# ALLPRINT-CAPBOARD-677512-SIGNAL-INPUTS.net
KiCad netlist of a schematic drawn in Altium Designer
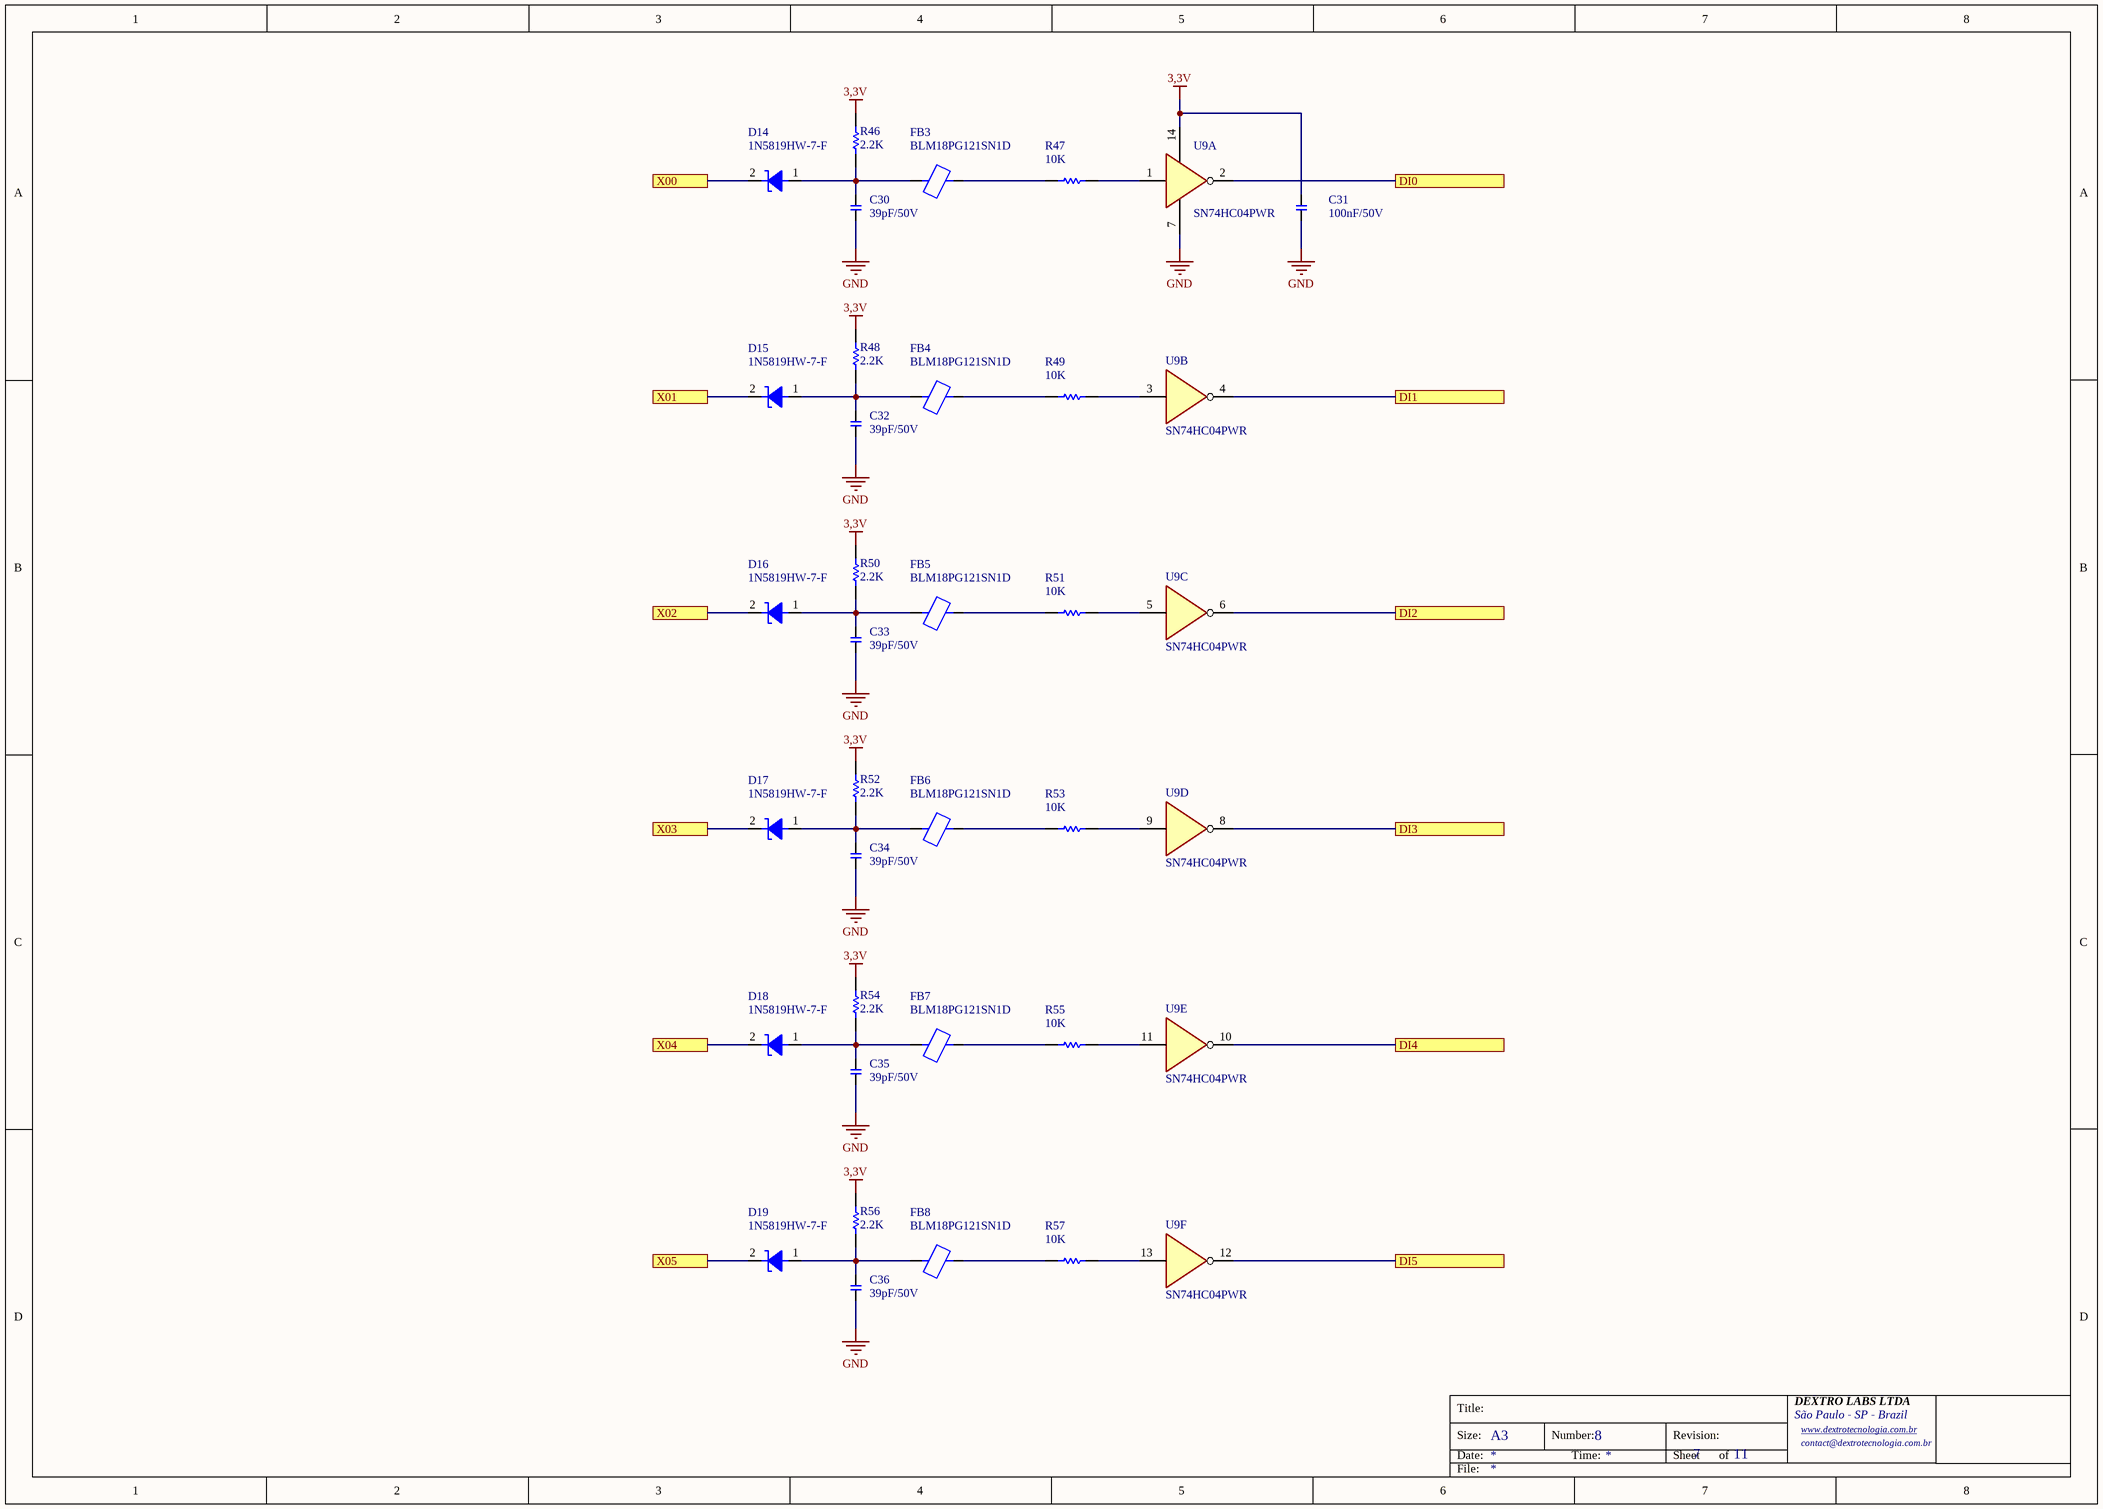
[diagram p0: ALLPRINT-CAPBOARD-677512-SIGNAL-INPUTS.SchDoc]

(export (version "E")
  (design (tool "Eeschema 10.0.6"))
  (components
    (comp (ref "C30")
      (value "39pF/50V")
      (footprint "CAP-0603")
      (description "50V 39pF X7R ±10% 0603 Multilayer Ceramic Capacitors MLCC - SMD/SMT ROHS")
      (libsource (lib "dextro-labs") (part "CAP-39pF/50V-0603-X7R-MLCC"))
    )
    (comp (ref "C31")
      (value "100nF/50V")
      (footprint "CAP-0603")
      (description "50V 100nF X7R ±10% 0603 Multilayer Ceramic Capacitors MLCC - SMD/SMT ROHS")
      (libsource (lib "dextro-labs") (part "CAP-100nF/50V-0603-X7R-MLCC"))
    )
    (comp (ref "C32")
      (value "39pF/50V")
      (footprint "CAP-0603")
      (description "50V 39pF X7R ±10% 0603 Multilayer Ceramic Capacitors MLCC - SMD/SMT ROHS")
      (libsource (lib "dextro-labs") (part "CAP-39pF/50V-0603-X7R-MLCC"))
    )
    (comp (ref "C33")
      (value "39pF/50V")
      (footprint "CAP-0603")
      (description "50V 39pF X7R ±10% 0603 Multilayer Ceramic Capacitors MLCC - SMD/SMT ROHS")
      (libsource (lib "dextro-labs") (part "CAP-39pF/50V-0603-X7R-MLCC"))
    )
    (comp (ref "C34")
      (value "39pF/50V")
      (footprint "CAP-0603")
      (description "50V 39pF X7R ±10% 0603 Multilayer Ceramic Capacitors MLCC - SMD/SMT ROHS")
      (libsource (lib "dextro-labs") (part "CAP-39pF/50V-0603-X7R-MLCC"))
    )
    (comp (ref "C35")
      (value "39pF/50V")
      (footprint "CAP-0603")
      (description "50V 39pF X7R ±10% 0603 Multilayer Ceramic Capacitors MLCC - SMD/SMT ROHS")
      (libsource (lib "dextro-labs") (part "CAP-39pF/50V-0603-X7R-MLCC"))
    )
    (comp (ref "C36")
      (value "39pF/50V")
      (footprint "CAP-0603")
      (description "50V 39pF X7R ±10% 0603 Multilayer Ceramic Capacitors MLCC - SMD/SMT ROHS")
      (libsource (lib "dextro-labs") (part "CAP-39pF/50V-0603-X7R-MLCC"))
    )
    (comp (ref "D14")
      (value "1N5819HW-7-F")
      (footprint "SOD123")
      (description "25A 1 Independent 40V 450mV@1A 1A SOD-123 Single Diodes RoHS")
      (libsource (lib "dextro-labs") (part "1N5819HW-7-F"))
    )
    (comp (ref "D15")
      (value "1N5819HW-7-F")
      (footprint "SOD123")
      (description "25A 1 Independent 40V 450mV@1A 1A SOD-123 Single Diodes RoHS")
      (libsource (lib "dextro-labs") (part "1N5819HW-7-F"))
    )
    (comp (ref "D16")
      (value "1N5819HW-7-F")
      (footprint "SOD123")
      (description "25A 1 Independent 40V 450mV@1A 1A SOD-123 Single Diodes RoHS")
      (libsource (lib "dextro-labs") (part "1N5819HW-7-F"))
    )
    (comp (ref "D17")
      (value "1N5819HW-7-F")
      (footprint "SOD123")
      (description "25A 1 Independent 40V 450mV@1A 1A SOD-123 Single Diodes RoHS")
      (libsource (lib "dextro-labs") (part "1N5819HW-7-F"))
    )
    (comp (ref "D18")
      (value "1N5819HW-7-F")
      (footprint "SOD123")
      (description "25A 1 Independent 40V 450mV@1A 1A SOD-123 Single Diodes RoHS")
      (libsource (lib "dextro-labs") (part "1N5819HW-7-F"))
    )
    (comp (ref "D19")
      (value "1N5819HW-7-F")
      (footprint "SOD123")
      (description "25A 1 Independent 40V 450mV@1A 1A SOD-123 Single Diodes RoHS")
      (libsource (lib "dextro-labs") (part "1N5819HW-7-F"))
    )
    (comp (ref "FB3")
      (value "BLM18PG121SN1D")
      (footprint "RES-0603")
      (description "FERRITE BEAD 120Ω 0603 1LN")
      (libsource (lib "dextro-labs") (part "BLM18PG121SN1D"))
    )
    (comp (ref "FB4")
      (value "BLM18PG121SN1D")
      (footprint "RES-0603")
      (description "FERRITE BEAD 120Ω 0603 1LN")
      (libsource (lib "dextro-labs") (part "BLM18PG121SN1D"))
    )
    (comp (ref "FB5")
      (value "BLM18PG121SN1D")
      (footprint "RES-0603")
      (description "FERRITE BEAD 120Ω 0603 1LN")
      (libsource (lib "dextro-labs") (part "BLM18PG121SN1D"))
    )
    (comp (ref "FB6")
      (value "BLM18PG121SN1D")
      (footprint "RES-0603")
      (description "FERRITE BEAD 120Ω 0603 1LN")
      (libsource (lib "dextro-labs") (part "BLM18PG121SN1D"))
    )
    (comp (ref "FB7")
      (value "BLM18PG121SN1D")
      (footprint "RES-0603")
      (description "FERRITE BEAD 120Ω 0603 1LN")
      (libsource (lib "dextro-labs") (part "BLM18PG121SN1D"))
    )
    (comp (ref "FB8")
      (value "BLM18PG121SN1D")
      (footprint "RES-0603")
      (description "FERRITE BEAD 120Ω 0603 1LN")
      (libsource (lib "dextro-labs") (part "BLM18PG121SN1D"))
    )
    (comp (ref "R46")
      (value "2.2K")
      (footprint "RES-0805")
      (description "125mW 2.2kΩ 150V ±100ppm/℃ Thick Film Resistor ±1% 0805 Chip Resistor - Surface Mount ROHS")
      (libsource (lib "dextro-labs") (part "RES-2.2K-1%-125mW-0805"))
    )
    (comp (ref "R47")
      (value "10K")
      (footprint "RES-0603")
      (description "100mW Thick Film Resistor 75V ±100ppm/℃ ±1% 10kΩ 0603 Chip Resistor - Surface Mount ROHS")
      (libsource (lib "dextro-labs") (part "RES-10K-1%-100mW-0603"))
    )
    (comp (ref "R48")
      (value "2.2K")
      (footprint "RES-0805")
      (description "125mW 2.2kΩ 150V ±100ppm/℃ Thick Film Resistor ±1% 0805 Chip Resistor - Surface Mount ROHS")
      (libsource (lib "dextro-labs") (part "RES-2.2K-1%-125mW-0805"))
    )
    (comp (ref "R49")
      (value "10K")
      (footprint "RES-0603")
      (description "100mW Thick Film Resistor 75V ±100ppm/℃ ±1% 10kΩ 0603 Chip Resistor - Surface Mount ROHS")
      (libsource (lib "dextro-labs") (part "RES-10K-1%-100mW-0603"))
    )
    (comp (ref "R50")
      (value "2.2K")
      (footprint "RES-0805")
      (description "125mW 2.2kΩ 150V ±100ppm/℃ Thick Film Resistor ±1% 0805 Chip Resistor - Surface Mount ROHS")
      (libsource (lib "dextro-labs") (part "RES-2.2K-1%-125mW-0805"))
    )
    (comp (ref "R51")
      (value "10K")
      (footprint "RES-0603")
      (description "100mW Thick Film Resistor 75V ±100ppm/℃ ±1% 10kΩ 0603 Chip Resistor - Surface Mount ROHS")
      (libsource (lib "dextro-labs") (part "RES-10K-1%-100mW-0603"))
    )
    (comp (ref "R52")
      (value "2.2K")
      (footprint "RES-0805")
      (description "125mW 2.2kΩ 150V ±100ppm/℃ Thick Film Resistor ±1% 0805 Chip Resistor - Surface Mount ROHS")
      (libsource (lib "dextro-labs") (part "RES-2.2K-1%-125mW-0805"))
    )
    (comp (ref "R53")
      (value "10K")
      (footprint "RES-0603")
      (description "100mW Thick Film Resistor 75V ±100ppm/℃ ±1% 10kΩ 0603 Chip Resistor - Surface Mount ROHS")
      (libsource (lib "dextro-labs") (part "RES-10K-1%-100mW-0603"))
    )
    (comp (ref "R54")
      (value "2.2K")
      (footprint "RES-0805")
      (description "125mW 2.2kΩ 150V ±100ppm/℃ Thick Film Resistor ±1% 0805 Chip Resistor - Surface Mount ROHS")
      (libsource (lib "dextro-labs") (part "RES-2.2K-1%-125mW-0805"))
    )
    (comp (ref "R55")
      (value "10K")
      (footprint "RES-0603")
      (description "100mW Thick Film Resistor 75V ±100ppm/℃ ±1% 10kΩ 0603 Chip Resistor - Surface Mount ROHS")
      (libsource (lib "dextro-labs") (part "RES-10K-1%-100mW-0603"))
    )
    (comp (ref "R56")
      (value "2.2K")
      (footprint "RES-0805")
      (description "125mW 2.2kΩ 150V ±100ppm/℃ Thick Film Resistor ±1% 0805 Chip Resistor - Surface Mount ROHS")
      (libsource (lib "dextro-labs") (part "RES-2.2K-1%-125mW-0805"))
    )
    (comp (ref "R57")
      (value "10K")
      (footprint "RES-0603")
      (description "100mW Thick Film Resistor 75V ±100ppm/℃ ±1% 10kΩ 0603 Chip Resistor - Surface Mount ROHS")
      (libsource (lib "dextro-labs") (part "RES-10K-1%-100mW-0603"))
    )
    (comp (ref "U9")
      (value "SN74HC04PWR")
      (footprint "TSSOP-14")
      (description "2V~6V 16ns@6V,50pF 2uA 6 1 TSSOP-14 Gates and Inverters RoHS")
      (libsource (lib "dextro-labs") (part "SN74HC04PWR"))
    )
  )
  (nets
    (net (code "1") (name "/DI0") (class "Default")
      (node (ref "U9") (pin "2") (pinfunction "1Y_2") (pintype "passive"))
    )
    (net (code "2") (name "/DI1") (class "Default")
      (node (ref "U9") (pin "4") (pinfunction "2Y_4") (pintype "passive"))
    )
    (net (code "3") (name "/DI2") (class "Default")
      (node (ref "U9") (pin "6") (pinfunction "3Y_6") (pintype "passive"))
    )
    (net (code "4") (name "/DI3") (class "Default")
      (node (ref "U9") (pin "8") (pinfunction "4Y_8") (pintype "passive"))
    )
    (net (code "5") (name "/DI4") (class "Default")
      (node (ref "U9") (pin "10") (pinfunction "5Y_10") (pintype "passive"))
    )
    (net (code "6") (name "/DI5") (class "Default")
      (node (ref "U9") (pin "12") (pinfunction "6Y_12") (pintype "passive"))
    )
    (net (code "7") (name "/X00") (class "Default")
      (node (ref "D14") (pin "2") (pinfunction "2_2") (pintype "passive"))
    )
    (net (code "8") (name "/X01") (class "Default")
      (node (ref "D15") (pin "2") (pinfunction "2_2") (pintype "passive"))
    )
    (net (code "9") (name "/X02") (class "Default")
      (node (ref "D16") (pin "2") (pinfunction "2_2") (pintype "passive"))
    )
    (net (code "10") (name "/X03") (class "Default")
      (node (ref "D17") (pin "2") (pinfunction "2_2") (pintype "passive"))
    )
    (net (code "11") (name "/X04") (class "Default")
      (node (ref "D18") (pin "2") (pinfunction "2_2") (pintype "passive"))
    )
    (net (code "12") (name "/X05") (class "Default")
      (node (ref "D19") (pin "2") (pinfunction "2_2") (pintype "passive"))
    )
    (net (code "13") (name "3,3V") (class "Default")
      (node (ref "C31") (pin "2") (pinfunction "2_2") (pintype "passive"))
      (node (ref "R46") (pin "1") (pinfunction "1_1") (pintype "passive"))
      (node (ref "R48") (pin "1") (pinfunction "1_1") (pintype "passive"))
      (node (ref "R50") (pin "1") (pinfunction "1_1") (pintype "passive"))
      (node (ref "R52") (pin "1") (pinfunction "1_1") (pintype "passive"))
      (node (ref "R54") (pin "1") (pinfunction "1_1") (pintype "passive"))
      (node (ref "R56") (pin "1") (pinfunction "1_1") (pintype "passive"))
      (node (ref "U9") (pin "14") (pinfunction "VCC_14") (pintype "passive"))
    )
    (net (code "14") (name "GND") (class "Default")
      (node (ref "C30") (pin "1") (pinfunction "1_1") (pintype "passive"))
      (node (ref "C31") (pin "1") (pinfunction "1_1") (pintype "passive"))
      (node (ref "C32") (pin "1") (pinfunction "1_1") (pintype "passive"))
      (node (ref "C33") (pin "1") (pinfunction "1_1") (pintype "passive"))
      (node (ref "C34") (pin "1") (pinfunction "1_1") (pintype "passive"))
      (node (ref "C35") (pin "1") (pinfunction "1_1") (pintype "passive"))
      (node (ref "C36") (pin "1") (pinfunction "1_1") (pintype "passive"))
      (node (ref "U9") (pin "7") (pinfunction "GND_7") (pintype "passive"))
    )
    (net (code "15") (name "Net-(C30-Pad2)") (class "Default")
      (node (ref "C30") (pin "2") (pinfunction "2_2") (pintype "passive"))
      (node (ref "D14") (pin "1") (pinfunction "1_1") (pintype "passive"))
      (node (ref "FB3") (pin "1") (pinfunction "1_1") (pintype "passive"))
      (node (ref "R46") (pin "2") (pinfunction "2_2") (pintype "passive"))
    )
    (net (code "16") (name "Net-(C32-Pad2)") (class "Default")
      (node (ref "C32") (pin "2") (pinfunction "2_2") (pintype "passive"))
      (node (ref "D15") (pin "1") (pinfunction "1_1") (pintype "passive"))
      (node (ref "FB4") (pin "1") (pinfunction "1_1") (pintype "passive"))
      (node (ref "R48") (pin "2") (pinfunction "2_2") (pintype "passive"))
    )
    (net (code "17") (name "Net-(C33-Pad2)") (class "Default")
      (node (ref "C33") (pin "2") (pinfunction "2_2") (pintype "passive"))
      (node (ref "D16") (pin "1") (pinfunction "1_1") (pintype "passive"))
      (node (ref "FB5") (pin "1") (pinfunction "1_1") (pintype "passive"))
      (node (ref "R50") (pin "2") (pinfunction "2_2") (pintype "passive"))
    )
    (net (code "18") (name "Net-(C34-Pad2)") (class "Default")
      (node (ref "C34") (pin "2") (pinfunction "2_2") (pintype "passive"))
      (node (ref "D17") (pin "1") (pinfunction "1_1") (pintype "passive"))
      (node (ref "FB6") (pin "1") (pinfunction "1_1") (pintype "passive"))
      (node (ref "R52") (pin "2") (pinfunction "2_2") (pintype "passive"))
    )
    (net (code "19") (name "Net-(C35-Pad2)") (class "Default")
      (node (ref "C35") (pin "2") (pinfunction "2_2") (pintype "passive"))
      (node (ref "D18") (pin "1") (pinfunction "1_1") (pintype "passive"))
      (node (ref "FB7") (pin "1") (pinfunction "1_1") (pintype "passive"))
      (node (ref "R54") (pin "2") (pinfunction "2_2") (pintype "passive"))
    )
    (net (code "20") (name "Net-(C36-Pad2)") (class "Default")
      (node (ref "C36") (pin "2") (pinfunction "2_2") (pintype "passive"))
      (node (ref "D19") (pin "1") (pinfunction "1_1") (pintype "passive"))
      (node (ref "FB8") (pin "1") (pinfunction "1_1") (pintype "passive"))
      (node (ref "R56") (pin "2") (pinfunction "2_2") (pintype "passive"))
    )
    (net (code "21") (name "Net-(FB3-Pad2)") (class "Default")
      (node (ref "FB3") (pin "2") (pinfunction "2_2") (pintype "passive"))
      (node (ref "R47") (pin "1") (pinfunction "1_1") (pintype "passive"))
    )
    (net (code "22") (name "Net-(FB4-Pad2)") (class "Default")
      (node (ref "FB4") (pin "2") (pinfunction "2_2") (pintype "passive"))
      (node (ref "R49") (pin "1") (pinfunction "1_1") (pintype "passive"))
    )
    (net (code "23") (name "Net-(FB5-Pad2)") (class "Default")
      (node (ref "FB5") (pin "2") (pinfunction "2_2") (pintype "passive"))
      (node (ref "R51") (pin "1") (pinfunction "1_1") (pintype "passive"))
    )
    (net (code "24") (name "Net-(FB6-Pad2)") (class "Default")
      (node (ref "FB6") (pin "2") (pinfunction "2_2") (pintype "passive"))
      (node (ref "R53") (pin "1") (pinfunction "1_1") (pintype "passive"))
    )
    (net (code "25") (name "Net-(FB7-Pad2)") (class "Default")
      (node (ref "FB7") (pin "2") (pinfunction "2_2") (pintype "passive"))
      (node (ref "R55") (pin "1") (pinfunction "1_1") (pintype "passive"))
    )
    (net (code "26") (name "Net-(FB8-Pad2)") (class "Default")
      (node (ref "FB8") (pin "2") (pinfunction "2_2") (pintype "passive"))
      (node (ref "R57") (pin "1") (pinfunction "1_1") (pintype "passive"))
    )
    (net (code "27") (name "Net-(U9A-1A)") (class "Default")
      (node (ref "R47") (pin "2") (pinfunction "2_2") (pintype "passive"))
      (node (ref "U9") (pin "1") (pinfunction "1A_1") (pintype "passive"))
    )
    (net (code "28") (name "Net-(U9B-2A)") (class "Default")
      (node (ref "R49") (pin "2") (pinfunction "2_2") (pintype "passive"))
      (node (ref "U9") (pin "3") (pinfunction "2A_3") (pintype "passive"))
    )
    (net (code "29") (name "Net-(U9C-3A)") (class "Default")
      (node (ref "R51") (pin "2") (pinfunction "2_2") (pintype "passive"))
      (node (ref "U9") (pin "5") (pinfunction "3A_5") (pintype "passive"))
    )
    (net (code "30") (name "Net-(U9D-4A)") (class "Default")
      (node (ref "R53") (pin "2") (pinfunction "2_2") (pintype "passive"))
      (node (ref "U9") (pin "9") (pinfunction "4A_9") (pintype "passive"))
    )
    (net (code "31") (name "Net-(U9E-5A)") (class "Default")
      (node (ref "R55") (pin "2") (pinfunction "2_2") (pintype "passive"))
      (node (ref "U9") (pin "11") (pinfunction "5A_11") (pintype "passive"))
    )
    (net (code "32") (name "Net-(U9F-6A)") (class "Default")
      (node (ref "R57") (pin "2") (pinfunction "2_2") (pintype "passive"))
      (node (ref "U9") (pin "13") (pinfunction "6A_13") (pintype "passive"))
    )
  )
)
